# 7SEG.net
KiCad netlist of a schematic drawn in Altium Designer
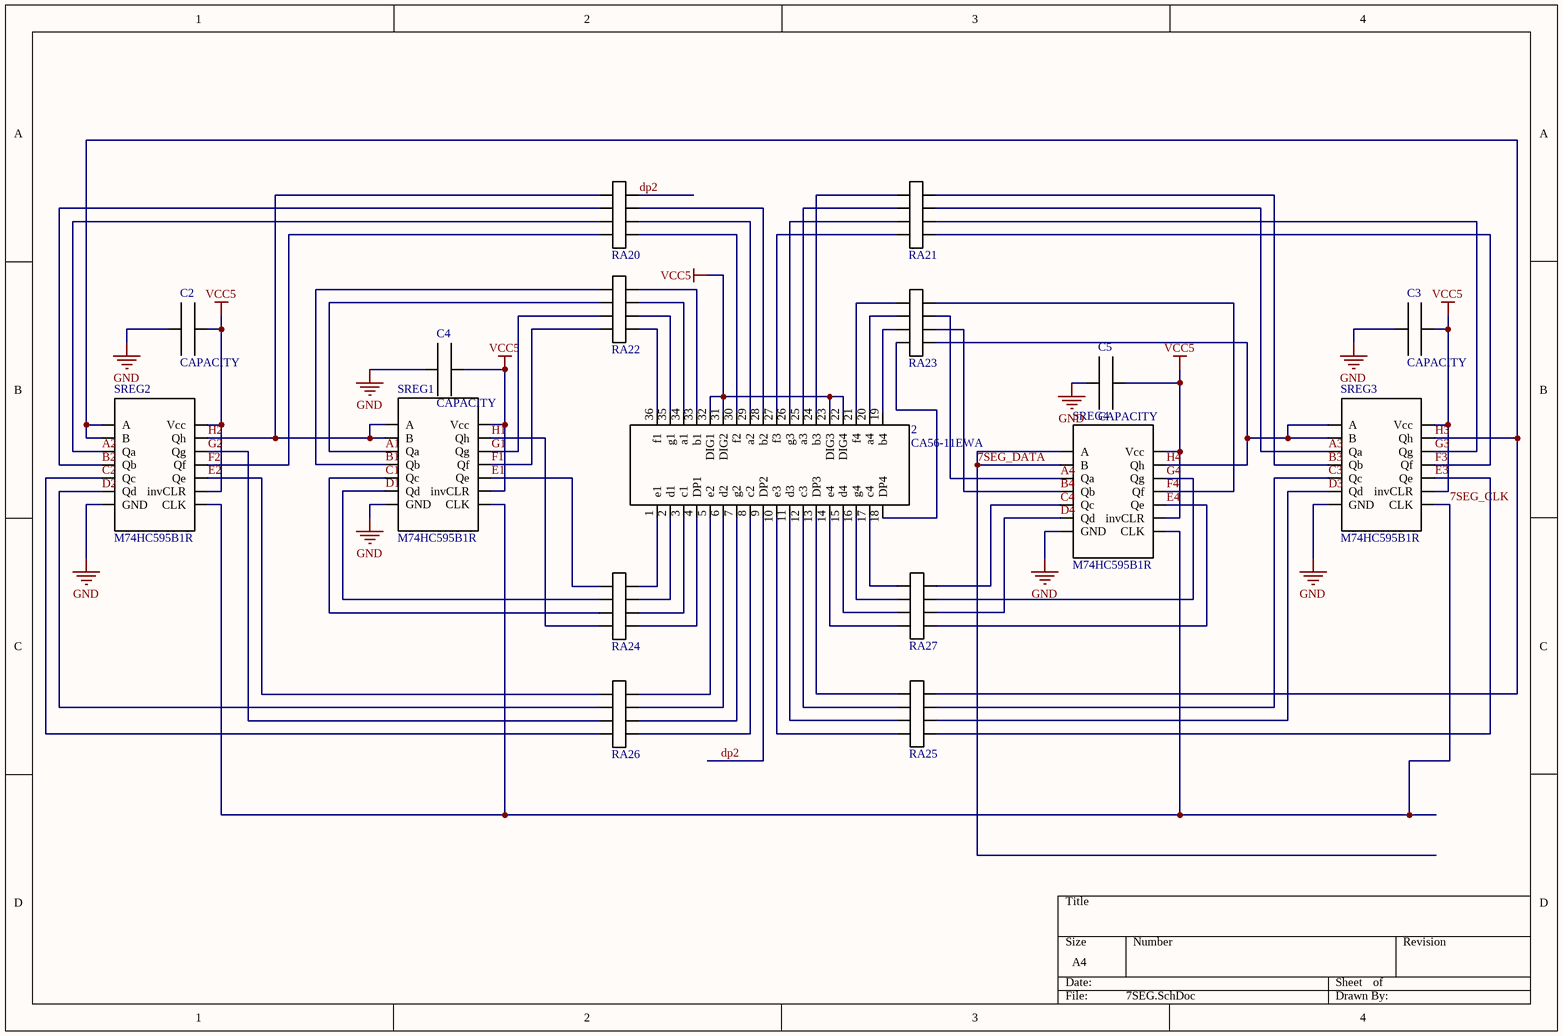
[diagram p0: 7SEG.SchDoc]

(export (version "E")
  (design (tool "Eeschema 10.0.6"))
  (components
    (comp (ref "2")
      (value "CA56-11EWA")
      (footprint "PcbLib1:CA56-11EWA")
      (libsource (lib "elvis_lib") (part "CA56-11EWA"))
    )
    (comp (ref "C2")
      (value "CAPACITY")
      (footprint "elvis_lib:R0805")
      (libsource (lib "elvis_lib") (part "CAPACITY"))
    )
    (comp (ref "C3")
      (value "CAPACITY")
      (footprint "elvis_lib:R0805")
      (libsource (lib "elvis_lib") (part "CAPACITY"))
    )
    (comp (ref "C4")
      (value "CAPACITY")
      (footprint "elvis_lib:R0805")
      (libsource (lib "elvis_lib") (part "CAPACITY"))
    )
    (comp (ref "C5")
      (value "CAPACITY")
      (footprint "elvis_lib:R0805")
      (libsource (lib "elvis_lib") (part "CAPACITY"))
    )
    (comp (ref "RA20")
      (value "Bourns CAT16-102J4LF_1")
      (footprint "CAT16-102J4_NEW")
      (libsource (lib "elvis_lib") (part "Bourns CAT16-102J4LF_1"))
    )
    (comp (ref "RA21")
      (value "Bourns CAT16-102J4LF_1")
      (footprint "CAT16-102J4_NEW")
      (libsource (lib "elvis_lib") (part "Bourns CAT16-102J4LF_1"))
    )
    (comp (ref "RA22")
      (value "Bourns CAT16-102J4LF_1")
      (footprint "CAT16-102J4_NEW")
      (libsource (lib "elvis_lib") (part "Bourns CAT16-102J4LF_1"))
    )
    (comp (ref "RA23")
      (value "Bourns CAT16-102J4LF_1")
      (footprint "CAT16-102J4_NEW")
      (libsource (lib "elvis_lib") (part "Bourns CAT16-102J4LF_1"))
    )
    (comp (ref "RA24")
      (value "Bourns CAT16-102J4LF_1")
      (footprint "CAT16-102J4_NEW")
      (libsource (lib "elvis_lib") (part "Bourns CAT16-102J4LF_1"))
    )
    (comp (ref "RA25")
      (value "Bourns CAT16-102J4LF_1")
      (footprint "CAT16-102J4_NEW")
      (libsource (lib "elvis_lib") (part "Bourns CAT16-102J4LF_1"))
    )
    (comp (ref "RA26")
      (value "Bourns CAT16-102J4LF_1")
      (footprint "CAT16-102J4_NEW")
      (libsource (lib "elvis_lib") (part "Bourns CAT16-102J4LF_1"))
    )
    (comp (ref "RA27")
      (value "Bourns CAT16-102J4LF_1")
      (footprint "CAT16-102J4_NEW")
      (libsource (lib "elvis_lib") (part "Bourns CAT16-102J4LF_1"))
    )
    (comp (ref "SREG1")
      (value "M74HC595B1R")
      (footprint "SN74HC164DRX")
      (libsource (lib "elvis_lib") (part "M74HC595B1R"))
    )
    (comp (ref "SREG2")
      (value "M74HC595B1R")
      (footprint "SN74HC164DRX")
      (libsource (lib "elvis_lib") (part "M74HC595B1R"))
    )
    (comp (ref "SREG3")
      (value "M74HC595B1R")
      (footprint "SN74HC164DRX")
      (libsource (lib "elvis_lib") (part "M74HC595B1R"))
    )
    (comp (ref "SREG4")
      (value "M74HC595B1R")
      (footprint "SN74HC164DRX")
      (libsource (lib "elvis_lib") (part "M74HC595B1R"))
    )
  )
  (nets
    (net (code "1") (name "/7SEG_CLK") (class "Default")
      (node (ref "SREG1") (pin "8") (pinfunction "CLK_8") (pintype "passive"))
      (node (ref "SREG2") (pin "8") (pinfunction "CLK_8") (pintype "passive"))
      (node (ref "SREG3") (pin "8") (pinfunction "CLK_8") (pintype "passive"))
      (node (ref "SREG4") (pin "8") (pinfunction "CLK_8") (pintype "passive"))
    )
    (net (code "2") (name "/7SEG_DATA") (class "Default")
      (node (ref "SREG4") (pin "1") (pinfunction "A_1") (pintype "passive"))
      (node (ref "SREG4") (pin "2") (pinfunction "B_2") (pintype "passive"))
    )
    (net (code "3") (name "/A1") (class "Default")
      (node (ref "RA22") (pin "2") (pinfunction "2_2") (pintype "passive"))
      (node (ref "SREG1") (pin "3") (pinfunction "Qa_3") (pintype "passive"))
    )
    (net (code "4") (name "/A2") (class "Default")
      (node (ref "RA20") (pin "6") (pinfunction "6_6") (pintype "passive"))
      (node (ref "SREG2") (pin "3") (pinfunction "Qa_3") (pintype "passive"))
    )
    (net (code "5") (name "/A3") (class "Default")
      (node (ref "RA21") (pin "2") (pinfunction "2_2") (pintype "passive"))
      (node (ref "SREG3") (pin "3") (pinfunction "Qa_3") (pintype "passive"))
    )
    (net (code "6") (name "/A4") (class "Default")
      (node (ref "RA23") (pin "2") (pinfunction "2_2") (pintype "passive"))
      (node (ref "SREG4") (pin "3") (pinfunction "Qa_3") (pintype "passive"))
    )
    (net (code "7") (name "/B1") (class "Default")
      (node (ref "RA22") (pin "3") (pinfunction "3_3") (pintype "passive"))
      (node (ref "SREG1") (pin "4") (pinfunction "Qb_4") (pintype "passive"))
    )
    (net (code "8") (name "/B2") (class "Default")
      (node (ref "RA20") (pin "5") (pinfunction "5_5") (pintype "passive"))
      (node (ref "SREG2") (pin "4") (pinfunction "Qb_4") (pintype "passive"))
    )
    (net (code "9") (name "/B3") (class "Default")
      (node (ref "RA21") (pin "3") (pinfunction "3_3") (pintype "passive"))
      (node (ref "SREG3") (pin "4") (pinfunction "Qb_4") (pintype "passive"))
    )
    (net (code "10") (name "/B4") (class "Default")
      (node (ref "RA23") (pin "1") (pinfunction "1_1") (pintype "passive"))
      (node (ref "SREG4") (pin "4") (pinfunction "Qb_4") (pintype "passive"))
    )
    (net (code "11") (name "/C1") (class "Default")
      (node (ref "RA24") (pin "1") (pinfunction "1_1") (pintype "passive"))
      (node (ref "SREG1") (pin "5") (pinfunction "Qc_5") (pintype "passive"))
    )
    (net (code "12") (name "/C2") (class "Default")
      (node (ref "RA26") (pin "3") (pinfunction "3_3") (pintype "passive"))
      (node (ref "SREG2") (pin "5") (pinfunction "Qc_5") (pintype "passive"))
    )
    (net (code "13") (name "/C3") (class "Default")
      (node (ref "RA25") (pin "5") (pinfunction "5_5") (pintype "passive"))
      (node (ref "SREG3") (pin "5") (pinfunction "Qc_5") (pintype "passive"))
    )
    (net (code "14") (name "/C4") (class "Default")
      (node (ref "RA27") (pin "7") (pinfunction "7_7") (pintype "passive"))
      (node (ref "SREG4") (pin "5") (pinfunction "Qc_5") (pintype "passive"))
    )
    (net (code "15") (name "/D1") (class "Default")
      (node (ref "RA24") (pin "2") (pinfunction "2_2") (pintype "passive"))
      (node (ref "SREG1") (pin "6") (pinfunction "Qd_6") (pintype "passive"))
    )
    (net (code "16") (name "/D2") (class "Default")
      (node (ref "RA26") (pin "1") (pinfunction "1_1") (pintype "passive"))
      (node (ref "SREG2") (pin "6") (pinfunction "Qd_6") (pintype "passive"))
    )
    (net (code "17") (name "/D3") (class "Default")
      (node (ref "RA25") (pin "6") (pinfunction "6_6") (pintype "passive"))
      (node (ref "SREG3") (pin "6") (pinfunction "Qd_6") (pintype "passive"))
    )
    (net (code "18") (name "/D4") (class "Default")
      (node (ref "RA27") (pin "5") (pinfunction "5_5") (pintype "passive"))
      (node (ref "SREG4") (pin "6") (pinfunction "Qd_6") (pintype "passive"))
    )
    (net (code "19") (name "/E1") (class "Default")
      (node (ref "RA24") (pin "3") (pinfunction "3_3") (pintype "passive"))
      (node (ref "SREG1") (pin "10") (pinfunction "Qe_10") (pintype "passive"))
    )
    (net (code "20") (name "/E2") (class "Default")
      (node (ref "RA26") (pin "0") (pinfunction "0_0") (pintype "passive"))
      (node (ref "SREG2") (pin "10") (pinfunction "Qe_10") (pintype "passive"))
    )
    (net (code "21") (name "/E3") (class "Default")
      (node (ref "RA25") (pin "7") (pinfunction "7_7") (pintype "passive"))
      (node (ref "SREG3") (pin "10") (pinfunction "Qe_10") (pintype "passive"))
    )
    (net (code "22") (name "/E4") (class "Default")
      (node (ref "RA27") (pin "4") (pinfunction "4_4") (pintype "passive"))
      (node (ref "SREG4") (pin "10") (pinfunction "Qe_10") (pintype "passive"))
    )
    (net (code "23") (name "/F1") (class "Default")
      (node (ref "RA22") (pin "0") (pinfunction "0_0") (pintype "passive"))
      (node (ref "SREG1") (pin "11") (pinfunction "Qf_11") (pintype "passive"))
    )
    (net (code "24") (name "/F2") (class "Default")
      (node (ref "RA20") (pin "7") (pinfunction "7_7") (pintype "passive"))
      (node (ref "SREG2") (pin "11") (pinfunction "Qf_11") (pintype "passive"))
    )
    (net (code "25") (name "/F3") (class "Default")
      (node (ref "RA21") (pin "0") (pinfunction "0_0") (pintype "passive"))
      (node (ref "SREG3") (pin "11") (pinfunction "Qf_11") (pintype "passive"))
    )
    (net (code "26") (name "/F4") (class "Default")
      (node (ref "RA23") (pin "3") (pinfunction "3_3") (pintype "passive"))
      (node (ref "SREG4") (pin "11") (pinfunction "Qf_11") (pintype "passive"))
    )
    (net (code "27") (name "/G1") (class "Default")
      (node (ref "RA22") (pin "1") (pinfunction "1_1") (pintype "passive"))
      (node (ref "SREG1") (pin "12") (pinfunction "Qg_12") (pintype "passive"))
    )
    (net (code "28") (name "/G2") (class "Default")
      (node (ref "RA26") (pin "2") (pinfunction "2_2") (pintype "passive"))
      (node (ref "SREG2") (pin "12") (pinfunction "Qg_12") (pintype "passive"))
    )
    (net (code "29") (name "/G3") (class "Default")
      (node (ref "RA21") (pin "1") (pinfunction "1_1") (pintype "passive"))
      (node (ref "SREG3") (pin "12") (pinfunction "Qg_12") (pintype "passive"))
    )
    (net (code "30") (name "/G4") (class "Default")
      (node (ref "RA27") (pin "6") (pinfunction "6_6") (pintype "passive"))
      (node (ref "SREG4") (pin "12") (pinfunction "Qg_12") (pintype "passive"))
    )
    (net (code "31") (name "/H1") (class "Default")
      (node (ref "RA24") (pin "0") (pinfunction "0_0") (pintype "passive"))
      (node (ref "SREG1") (pin "13") (pinfunction "Qh_13") (pintype "passive"))
    )
    (net (code "32") (name "/H2") (class "Default")
      (node (ref "RA20") (pin "4") (pinfunction "4_4") (pintype "passive"))
      (node (ref "SREG1") (pin "1") (pinfunction "A_1") (pintype "passive"))
      (node (ref "SREG1") (pin "2") (pinfunction "B_2") (pintype "passive"))
      (node (ref "SREG2") (pin "13") (pinfunction "Qh_13") (pintype "passive"))
    )
    (net (code "33") (name "/H3") (class "Default")
      (node (ref "RA25") (pin "4") (pinfunction "4_4") (pintype "passive"))
      (node (ref "SREG2") (pin "1") (pinfunction "A_1") (pintype "passive"))
      (node (ref "SREG2") (pin "2") (pinfunction "B_2") (pintype "passive"))
      (node (ref "SREG3") (pin "13") (pinfunction "Qh_13") (pintype "passive"))
    )
    (net (code "34") (name "/H4") (class "Default")
      (node (ref "RA23") (pin "0") (pinfunction "0_0") (pintype "passive"))
      (node (ref "SREG3") (pin "1") (pinfunction "A_1") (pintype "passive"))
      (node (ref "SREG3") (pin "2") (pinfunction "B_2") (pintype "passive"))
      (node (ref "SREG4") (pin "13") (pinfunction "Qh_13") (pintype "passive"))
    )
    (net (code "35") (name "/dp2") (class "Default")
      (node (ref "2") (pin "9") (pinfunction "DP2_9") (pintype "passive"))
      (node (ref "RA20") (pin "3") (pinfunction "3_3") (pintype "passive"))
    )
    (net (code "36") (name "GND") (class "Default")
      (node (ref "C2") (pin "1") (pinfunction "1_1") (pintype "passive"))
      (node (ref "C3") (pin "1") (pinfunction "1_1") (pintype "passive"))
      (node (ref "C4") (pin "1") (pinfunction "1_1") (pintype "passive"))
      (node (ref "C5") (pin "1") (pinfunction "1_1") (pintype "passive"))
      (node (ref "SREG1") (pin "7") (pinfunction "GND_7") (pintype "passive"))
      (node (ref "SREG2") (pin "7") (pinfunction "GND_7") (pintype "passive"))
      (node (ref "SREG3") (pin "7") (pinfunction "GND_7") (pintype "passive"))
      (node (ref "SREG4") (pin "7") (pinfunction "GND_7") (pintype "passive"))
    )
    (net (code "37") (name "Net-(2-DP1)") (class "Default")
      (node (ref "2") (pin "4") (pinfunction "DP1_4") (pintype "passive"))
      (node (ref "RA24") (pin "7") (pinfunction "7_7") (pintype "passive"))
    )
    (net (code "38") (name "Net-(2-DP3)") (class "Default")
      (node (ref "2") (pin "13") (pinfunction "DP3_13") (pintype "passive"))
      (node (ref "RA25") (pin "3") (pinfunction "3_3") (pintype "passive"))
    )
    (net (code "39") (name "Net-(2-DP4)") (class "Default")
      (node (ref "2") (pin "18") (pinfunction "DP4_18") (pintype "passive"))
      (node (ref "RA23") (pin "7") (pinfunction "7_7") (pintype "passive"))
    )
    (net (code "40") (name "Net-(2-a1)") (class "Default")
      (node (ref "2") (pin "34") (pinfunction "a1_34") (pintype "passive"))
      (node (ref "RA22") (pin "5") (pinfunction "5_5") (pintype "passive"))
    )
    (net (code "41") (name "Net-(2-a2)") (class "Default")
      (node (ref "2") (pin "29") (pinfunction "a2_29") (pintype "passive"))
      (node (ref "RA20") (pin "1") (pinfunction "1_1") (pintype "passive"))
    )
    (net (code "42") (name "Net-(2-a3)") (class "Default")
      (node (ref "2") (pin "25") (pinfunction "a3_25") (pintype "passive"))
      (node (ref "RA21") (pin "5") (pinfunction "5_5") (pintype "passive"))
    )
    (net (code "43") (name "Net-(2-a4)") (class "Default")
      (node (ref "2") (pin "20") (pinfunction "a4_20") (pintype "passive"))
      (node (ref "RA23") (pin "5") (pinfunction "5_5") (pintype "passive"))
    )
    (net (code "44") (name "Net-(2-b1)") (class "Default")
      (node (ref "2") (pin "33") (pinfunction "b1_33") (pintype "passive"))
      (node (ref "RA22") (pin "4") (pinfunction "4_4") (pintype "passive"))
    )
    (net (code "45") (name "Net-(2-b2)") (class "Default")
      (node (ref "2") (pin "28") (pinfunction "b2_28") (pintype "passive"))
      (node (ref "RA20") (pin "2") (pinfunction "2_2") (pintype "passive"))
    )
    (net (code "46") (name "Net-(2-b3)") (class "Default")
      (node (ref "2") (pin "24") (pinfunction "b3_24") (pintype "passive"))
      (node (ref "RA21") (pin "4") (pinfunction "4_4") (pintype "passive"))
    )
    (net (code "47") (name "Net-(2-b4)") (class "Default")
      (node (ref "2") (pin "19") (pinfunction "b4_19") (pintype "passive"))
      (node (ref "RA23") (pin "6") (pinfunction "6_6") (pintype "passive"))
    )
    (net (code "48") (name "Net-(2-c1)") (class "Default")
      (node (ref "2") (pin "3") (pinfunction "c1_3") (pintype "passive"))
      (node (ref "RA24") (pin "6") (pinfunction "6_6") (pintype "passive"))
    )
    (net (code "49") (name "Net-(2-c2)") (class "Default")
      (node (ref "2") (pin "8") (pinfunction "c2_8") (pintype "passive"))
      (node (ref "RA26") (pin "4") (pinfunction "4_4") (pintype "passive"))
    )
    (net (code "50") (name "Net-(2-c3)") (class "Default")
      (node (ref "2") (pin "12") (pinfunction "c3_12") (pintype "passive"))
      (node (ref "RA25") (pin "2") (pinfunction "2_2") (pintype "passive"))
    )
    (net (code "51") (name "Net-(2-c4)") (class "Default")
      (node (ref "2") (pin "17") (pinfunction "c4_17") (pintype "passive"))
      (node (ref "RA27") (pin "0") (pinfunction "0_0") (pintype "passive"))
    )
    (net (code "52") (name "Net-(2-d1)") (class "Default")
      (node (ref "2") (pin "2") (pinfunction "d1_2") (pintype "passive"))
      (node (ref "RA24") (pin "5") (pinfunction "5_5") (pintype "passive"))
    )
    (net (code "53") (name "Net-(2-d2)") (class "Default")
      (node (ref "2") (pin "6") (pinfunction "d2_6") (pintype "passive"))
      (node (ref "RA26") (pin "6") (pinfunction "6_6") (pintype "passive"))
    )
    (net (code "54") (name "Net-(2-d3)") (class "Default")
      (node (ref "2") (pin "11") (pinfunction "d3_11") (pintype "passive"))
      (node (ref "RA25") (pin "1") (pinfunction "1_1") (pintype "passive"))
    )
    (net (code "55") (name "Net-(2-d4)") (class "Default")
      (node (ref "2") (pin "15") (pinfunction "d4_15") (pintype "passive"))
      (node (ref "RA27") (pin "2") (pinfunction "2_2") (pintype "passive"))
    )
    (net (code "56") (name "Net-(2-e1)") (class "Default")
      (node (ref "2") (pin "1") (pinfunction "e1_1") (pintype "passive"))
      (node (ref "RA24") (pin "4") (pinfunction "4_4") (pintype "passive"))
    )
    (net (code "57") (name "Net-(2-e2)") (class "Default")
      (node (ref "2") (pin "5") (pinfunction "e2_5") (pintype "passive"))
      (node (ref "RA26") (pin "7") (pinfunction "7_7") (pintype "passive"))
    )
    (net (code "58") (name "Net-(2-e3)") (class "Default")
      (node (ref "2") (pin "10") (pinfunction "e3_10") (pintype "passive"))
      (node (ref "RA25") (pin "0") (pinfunction "0_0") (pintype "passive"))
    )
    (net (code "59") (name "Net-(2-e4)") (class "Default")
      (node (ref "2") (pin "14") (pinfunction "e4_14") (pintype "passive"))
      (node (ref "RA27") (pin "3") (pinfunction "3_3") (pintype "passive"))
    )
    (net (code "60") (name "Net-(2-f1)") (class "Default")
      (node (ref "2") (pin "36") (pinfunction "f1_36") (pintype "passive"))
      (node (ref "RA22") (pin "7") (pinfunction "7_7") (pintype "passive"))
    )
    (net (code "61") (name "Net-(2-f2)") (class "Default")
      (node (ref "2") (pin "30") (pinfunction "f2_30") (pintype "passive"))
      (node (ref "RA20") (pin "0") (pinfunction "0_0") (pintype "passive"))
    )
    (net (code "62") (name "Net-(2-f3)") (class "Default")
      (node (ref "2") (pin "27") (pinfunction "f3_27") (pintype "passive"))
      (node (ref "RA21") (pin "7") (pinfunction "7_7") (pintype "passive"))
    )
    (net (code "63") (name "Net-(2-f4)") (class "Default")
      (node (ref "2") (pin "21") (pinfunction "f4_21") (pintype "passive"))
      (node (ref "RA23") (pin "4") (pinfunction "4_4") (pintype "passive"))
    )
    (net (code "64") (name "Net-(2-g1)") (class "Default")
      (node (ref "2") (pin "35") (pinfunction "g1_35") (pintype "passive"))
      (node (ref "RA22") (pin "6") (pinfunction "6_6") (pintype "passive"))
    )
    (net (code "65") (name "Net-(2-g2)") (class "Default")
      (node (ref "2") (pin "7") (pinfunction "g2_7") (pintype "passive"))
      (node (ref "RA26") (pin "5") (pinfunction "5_5") (pintype "passive"))
    )
    (net (code "66") (name "Net-(2-g3)") (class "Default")
      (node (ref "2") (pin "26") (pinfunction "g3_26") (pintype "passive"))
      (node (ref "RA21") (pin "6") (pinfunction "6_6") (pintype "passive"))
    )
    (net (code "67") (name "Net-(2-g4)") (class "Default")
      (node (ref "2") (pin "16") (pinfunction "g4_16") (pintype "passive"))
      (node (ref "RA27") (pin "1") (pinfunction "1_1") (pintype "passive"))
    )
    (net (code "68") (name "VCC5") (class "Default")
      (node (ref "2") (pin "22") (pinfunction "DIG4_22") (pintype "passive"))
      (node (ref "2") (pin "23") (pinfunction "DIG3_23") (pintype "passive"))
      (node (ref "2") (pin "31") (pinfunction "DIG2_31") (pintype "passive"))
      (node (ref "2") (pin "32") (pinfunction "DIG1_32") (pintype "passive"))
      (node (ref "C2") (pin "2") (pinfunction "2_2") (pintype "passive"))
      (node (ref "C3") (pin "2") (pinfunction "2_2") (pintype "passive"))
      (node (ref "C4") (pin "2") (pinfunction "2_2") (pintype "passive"))
      (node (ref "C5") (pin "2") (pinfunction "2_2") (pintype "passive"))
      (node (ref "SREG1") (pin "14") (pinfunction "Vcc_14") (pintype "passive"))
      (node (ref "SREG1") (pin "9") (pinfunction "invCLR_9") (pintype "passive"))
      (node (ref "SREG2") (pin "14") (pinfunction "Vcc_14") (pintype "passive"))
      (node (ref "SREG2") (pin "9") (pinfunction "invCLR_9") (pintype "passive"))
      (node (ref "SREG3") (pin "14") (pinfunction "Vcc_14") (pintype "passive"))
      (node (ref "SREG3") (pin "9") (pinfunction "invCLR_9") (pintype "passive"))
      (node (ref "SREG4") (pin "14") (pinfunction "Vcc_14") (pintype "passive"))
      (node (ref "SREG4") (pin "9") (pinfunction "invCLR_9") (pintype "passive"))
    )
  )
)
